# 130801_AriloRX_0_0.net
KiCad netlist of a schematic drawn in EAGLE
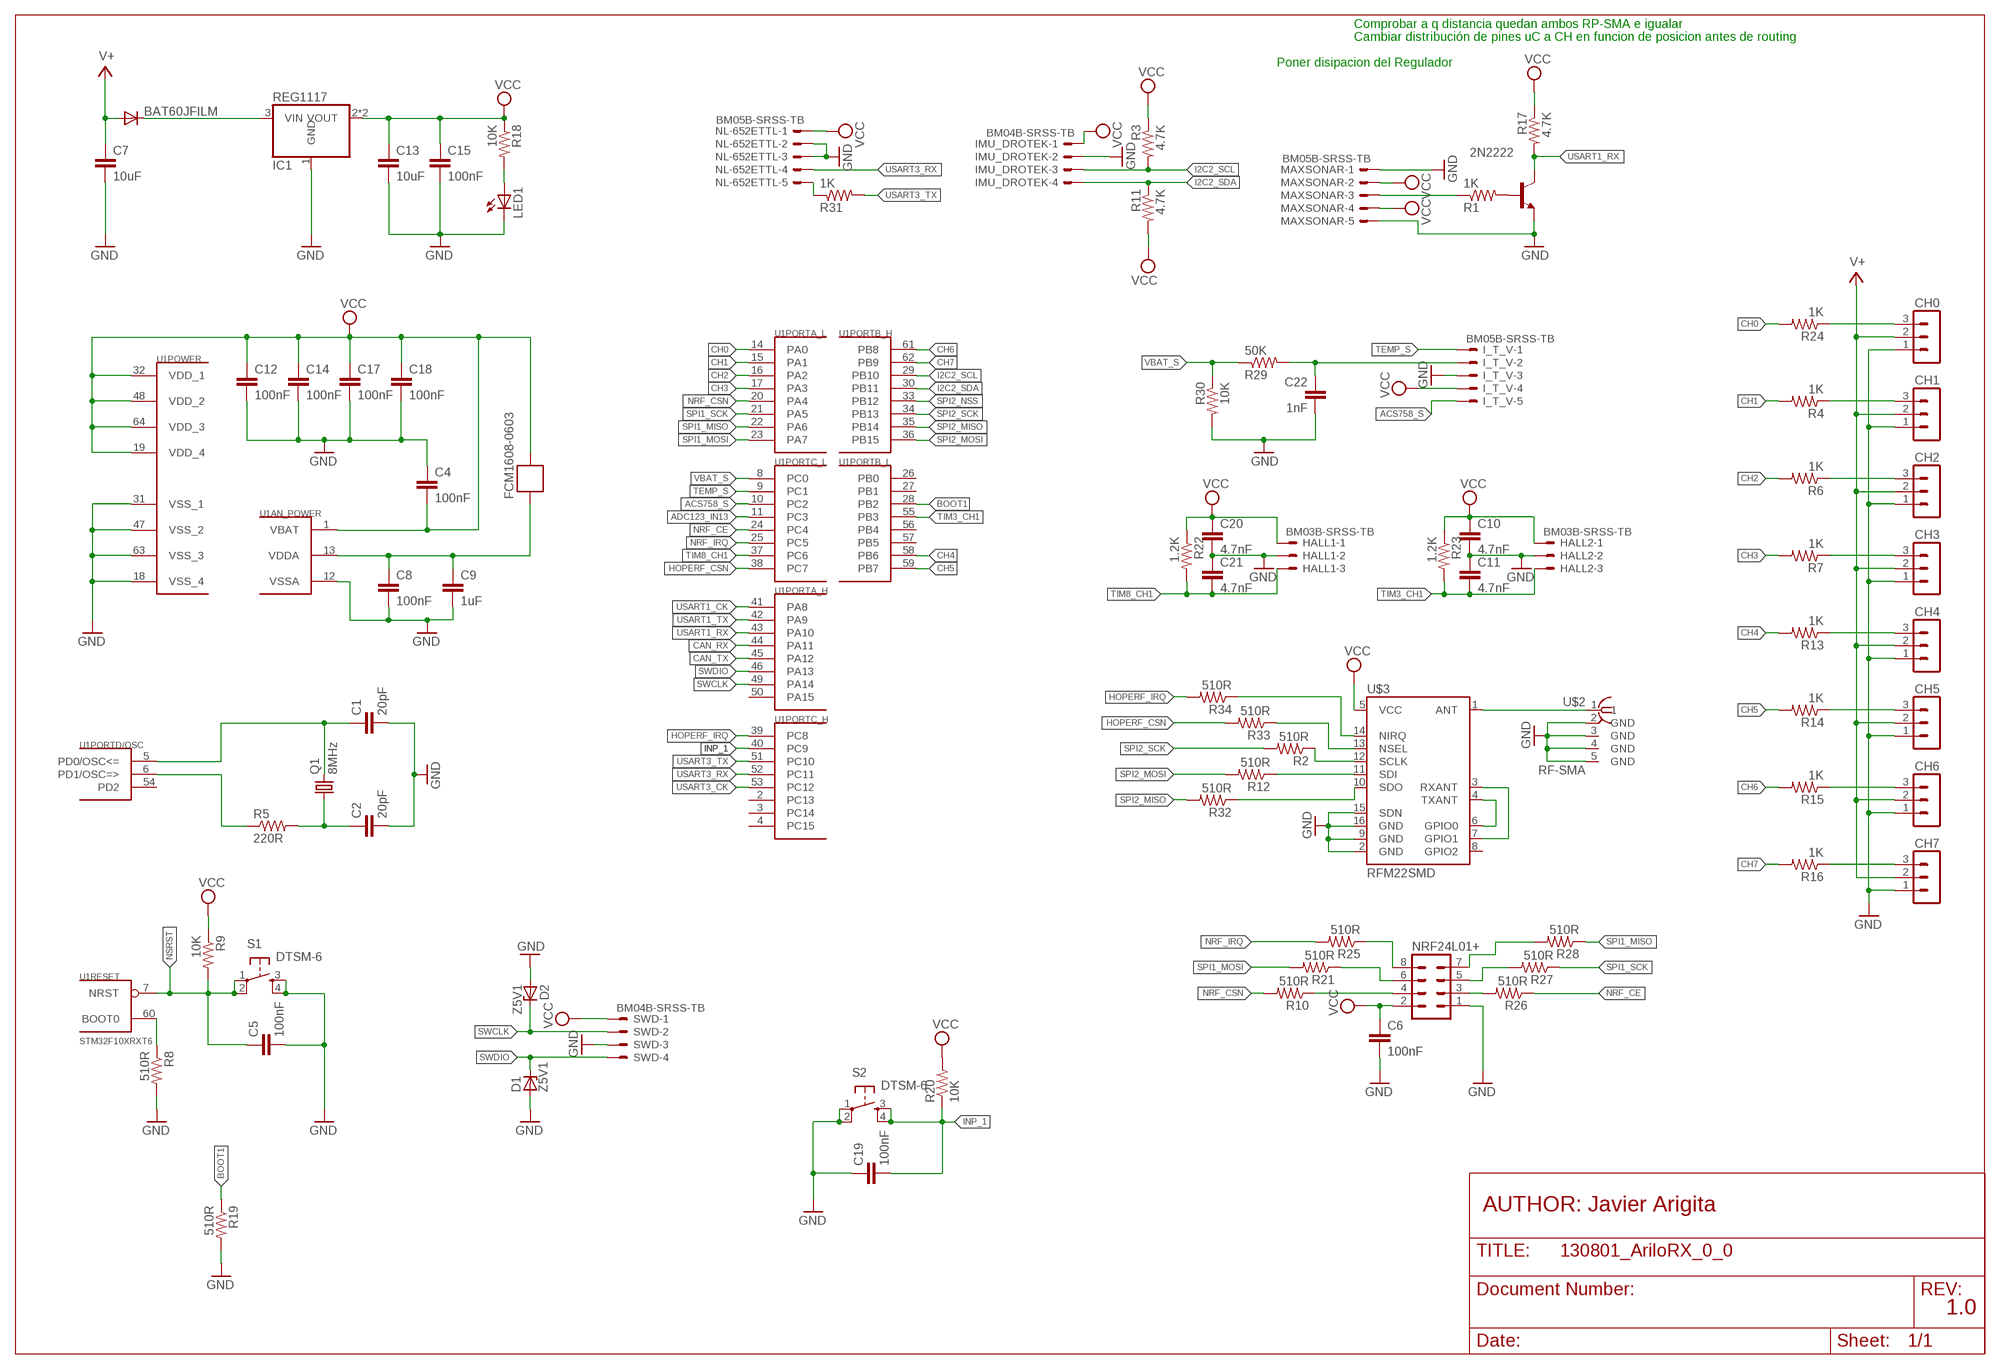
[diagram p0: schematic, sheet 1]

(export (version "E")
  (design (tool "Eeschema 10.0.6"))
  (components
    (comp (ref "2N2222")
      (value "MMBT2222ALT1-NPN-SOT23-BEC")
      (footprint "eagle-import:SOT23-BEC")
      (libsource (lib "eagle-import") (part "-NPN-SOT23-BECMMBT2222ALT1"))
    )
    (comp (ref "BAT60JFILM")
      (value "DIODE-SOD323-R")
      (footprint "eagle-import:SOD323-R")
      (libsource (lib "eagle-import") (part "DIODE-SOD323-R"))
    )
    (comp (ref "C1")
      (value "20pF")
      (footprint "eagle-import:C0805")
      (libsource (lib "eagle-import") (part "C-EUC0805"))
    )
    (comp (ref "C2")
      (value "20pF")
      (footprint "eagle-import:C0805")
      (libsource (lib "eagle-import") (part "C-EUC0805"))
    )
    (comp (ref "C4")
      (value "100nF")
      (footprint "eagle-import:C0805")
      (libsource (lib "eagle-import") (part "C-EUC0805"))
    )
    (comp (ref "C5")
      (value "100nF")
      (footprint "eagle-import:C0805")
      (libsource (lib "eagle-import") (part "C-EUC0805"))
    )
    (comp (ref "C6")
      (value "100nF")
      (footprint "eagle-import:C0805")
      (libsource (lib "eagle-import") (part "C-EUC0805"))
    )
    (comp (ref "C7")
      (value "10uF")
      (footprint "eagle-import:C3216")
      (libsource (lib "eagle-import") (part "resistor_C-EUC3216"))
    )
    (comp (ref "C8")
      (value "100nF")
      (footprint "eagle-import:C0805")
      (libsource (lib "eagle-import") (part "C-EUC0805"))
    )
    (comp (ref "C9")
      (value "1uF")
      (footprint "eagle-import:C3216")
      (libsource (lib "eagle-import") (part "resistor_C-EUC3216"))
    )
    (comp (ref "C10")
      (value "4.7nF")
      (footprint "eagle-import:C0805")
      (libsource (lib "eagle-import") (part "C-EUC0805"))
    )
    (comp (ref "C11")
      (value "4.7nF")
      (footprint "eagle-import:C0805")
      (libsource (lib "eagle-import") (part "C-EUC0805"))
    )
    (comp (ref "C12")
      (value "100nF")
      (footprint "eagle-import:C0805")
      (libsource (lib "eagle-import") (part "C-EUC0805"))
    )
    (comp (ref "C13")
      (value "10uF")
      (footprint "eagle-import:C3216")
      (libsource (lib "eagle-import") (part "resistor_C-EUC3216"))
    )
    (comp (ref "C14")
      (value "100nF")
      (footprint "eagle-import:C0805")
      (libsource (lib "eagle-import") (part "C-EUC0805"))
    )
    (comp (ref "C15")
      (value "100nF")
      (footprint "eagle-import:C0805")
      (libsource (lib "eagle-import") (part "C-EUC0805"))
    )
    (comp (ref "C17")
      (value "100nF")
      (footprint "eagle-import:C0805")
      (libsource (lib "eagle-import") (part "C-EUC0805"))
    )
    (comp (ref "C18")
      (value "100nF")
      (footprint "eagle-import:C0805")
      (libsource (lib "eagle-import") (part "C-EUC0805"))
    )
    (comp (ref "C19")
      (value "100nF")
      (footprint "eagle-import:C0805")
      (libsource (lib "eagle-import") (part "C-EUC0805"))
    )
    (comp (ref "C20")
      (value "4.7nF")
      (footprint "eagle-import:C0805")
      (libsource (lib "eagle-import") (part "C-EUC0805"))
    )
    (comp (ref "C21")
      (value "4.7nF")
      (footprint "eagle-import:C0805")
      (libsource (lib "eagle-import") (part "C-EUC0805"))
    )
    (comp (ref "C22")
      (value "1nF")
      (footprint "eagle-import:C0805")
      (libsource (lib "eagle-import") (part "C-EUC0805"))
    )
    (comp (ref "CH0")
      (value "MA03-1")
      (footprint "eagle-import:MA03-1")
      (libsource (lib "eagle-import") (part "MA03-1"))
    )
    (comp (ref "CH1")
      (value "MA03-1")
      (footprint "eagle-import:MA03-1")
      (libsource (lib "eagle-import") (part "MA03-1"))
    )
    (comp (ref "CH2")
      (value "MA03-1")
      (footprint "eagle-import:MA03-1")
      (libsource (lib "eagle-import") (part "MA03-1"))
    )
    (comp (ref "CH3")
      (value "MA03-1")
      (footprint "eagle-import:MA03-1")
      (libsource (lib "eagle-import") (part "MA03-1"))
    )
    (comp (ref "CH4")
      (value "MA03-1")
      (footprint "eagle-import:MA03-1")
      (libsource (lib "eagle-import") (part "MA03-1"))
    )
    (comp (ref "CH5")
      (value "MA03-1")
      (footprint "eagle-import:MA03-1")
      (libsource (lib "eagle-import") (part "MA03-1"))
    )
    (comp (ref "CH6")
      (value "MA03-1")
      (footprint "eagle-import:MA03-1")
      (libsource (lib "eagle-import") (part "MA03-1"))
    )
    (comp (ref "CH7")
      (value "MA03-1")
      (footprint "eagle-import:MA03-1")
      (libsource (lib "eagle-import") (part "MA03-1"))
    )
    (comp (ref "D1")
      (value "Z5V1")
      (footprint "eagle-import:SOD80C")
      (libsource (lib "eagle-import") (part "ZENER-DIODESOD80C"))
    )
    (comp (ref "D2")
      (value "Z5V1")
      (footprint "eagle-import:SOD80C")
      (libsource (lib "eagle-import") (part "ZENER-DIODESOD80C"))
    )
    (comp (ref "FCM1608-0603")
      (value "FERRITE-BEAD")
      (footprint "eagle-import:R0603")
      (libsource (lib "eagle-import") (part "FERRITE-BEAD"))
    )
    (comp (ref "HALL1")
      (value "BM03B-SRSS-TB")
      (footprint "eagle-import:BM03B-SRSS-TB")
      (libsource (lib "eagle-import") (part "?M03B-SRSS-TBB"))
    )
    (comp (ref "HALL2")
      (value "BM03B-SRSS-TB")
      (footprint "eagle-import:BM03B-SRSS-TB")
      (libsource (lib "eagle-import") (part "?M03B-SRSS-TBB"))
    )
    (comp (ref "IC1")
      (value "REG1117")
      (footprint "eagle-import:SOT223")
      (libsource (lib "eagle-import") (part "REG1117"))
    )
    (comp (ref "IMU_DROTEK")
      (value "BM04B-SRSS-TB")
      (footprint "eagle-import:BM04B-SRSS-TB")
      (libsource (lib "eagle-import") (part "?M04B-SRSS-TBB"))
    )
    (comp (ref "I_T_V")
      (value "BM05B-SRSS-TB")
      (footprint "eagle-import:BM05B-SRSS-TB")
      (libsource (lib "eagle-import") (part "?M05B-SRSS-TBB"))
    )
    (comp (ref "LED1")
      (value "LED0805")
      (footprint "eagle-import:CHIPLED_0805")
      (libsource (lib "eagle-import") (part "LED0805"))
    )
    (comp (ref "MAXSONAR")
      (value "BM05B-SRSS-TB")
      (footprint "eagle-import:BM05B-SRSS-TB")
      (libsource (lib "eagle-import") (part "?M05B-SRSS-TBB"))
    )
    (comp (ref "NL-652ETTL")
      (value "BM05B-SRSS-TB")
      (footprint "eagle-import:BM05B-SRSS-TB")
      (libsource (lib "eagle-import") (part "?M05B-SRSS-TBB"))
    )
    (comp (ref "NRF24L01+")
      (value "MA04-2")
      (footprint "eagle-import:MA04-2")
      (libsource (lib "eagle-import") (part "MA04-2"))
    )
    (comp (ref "Q1")
      (value "8MHz")
      (footprint "eagle-import:SM49")
      (libsource (lib "eagle-import") (part "CRYSTALSM49"))
    )
    (comp (ref "R1")
      (value "1K")
      (footprint "eagle-import:R0805")
      (libsource (lib "eagle-import") (part "RESISTOR0805"))
    )
    (comp (ref "R2")
      (value "510R")
      (footprint "eagle-import:R0805")
      (libsource (lib "eagle-import") (part "RESISTOR0805"))
    )
    (comp (ref "R3")
      (value "4.7K")
      (footprint "eagle-import:R0805")
      (libsource (lib "eagle-import") (part "RESISTOR0805"))
    )
    (comp (ref "R4")
      (value "1K")
      (footprint "eagle-import:R0805")
      (libsource (lib "eagle-import") (part "RESISTOR0805"))
    )
    (comp (ref "R5")
      (value "220R")
      (footprint "eagle-import:R0805")
      (libsource (lib "eagle-import") (part "RESISTOR0805"))
    )
    (comp (ref "R6")
      (value "1K")
      (footprint "eagle-import:R0805")
      (libsource (lib "eagle-import") (part "RESISTOR0805"))
    )
    (comp (ref "R7")
      (value "1K")
      (footprint "eagle-import:R0805")
      (libsource (lib "eagle-import") (part "RESISTOR0805"))
    )
    (comp (ref "R8")
      (value "510R")
      (footprint "eagle-import:R0805")
      (libsource (lib "eagle-import") (part "RESISTOR0805"))
    )
    (comp (ref "R9")
      (value "10K")
      (footprint "eagle-import:R0805")
      (libsource (lib "eagle-import") (part "RESISTOR0805"))
    )
    (comp (ref "R10")
      (value "510R")
      (footprint "eagle-import:R0805")
      (libsource (lib "eagle-import") (part "RESISTOR0805"))
    )
    (comp (ref "R11")
      (value "4.7K")
      (footprint "eagle-import:R0805")
      (libsource (lib "eagle-import") (part "RESISTOR0805"))
    )
    (comp (ref "R12")
      (value "510R")
      (footprint "eagle-import:R0805")
      (libsource (lib "eagle-import") (part "RESISTOR0805"))
    )
    (comp (ref "R13")
      (value "1K")
      (footprint "eagle-import:R0805")
      (libsource (lib "eagle-import") (part "RESISTOR0805"))
    )
    (comp (ref "R14")
      (value "1K")
      (footprint "eagle-import:R0805")
      (libsource (lib "eagle-import") (part "RESISTOR0805"))
    )
    (comp (ref "R15")
      (value "1K")
      (footprint "eagle-import:R0805")
      (libsource (lib "eagle-import") (part "RESISTOR0805"))
    )
    (comp (ref "R16")
      (value "1K")
      (footprint "eagle-import:R0805")
      (libsource (lib "eagle-import") (part "RESISTOR0805"))
    )
    (comp (ref "R17")
      (value "4.7K")
      (footprint "eagle-import:R0805")
      (libsource (lib "eagle-import") (part "RESISTOR0805"))
    )
    (comp (ref "R18")
      (value "10K")
      (footprint "eagle-import:R0805")
      (libsource (lib "eagle-import") (part "RESISTOR0805"))
    )
    (comp (ref "R19")
      (value "510R")
      (footprint "eagle-import:R0805")
      (libsource (lib "eagle-import") (part "RESISTOR0805"))
    )
    (comp (ref "R20")
      (value "10K")
      (footprint "eagle-import:R0805")
      (libsource (lib "eagle-import") (part "RESISTOR0805"))
    )
    (comp (ref "R21")
      (value "510R")
      (footprint "eagle-import:R0805")
      (libsource (lib "eagle-import") (part "RESISTOR0805"))
    )
    (comp (ref "R22")
      (value "1.2K")
      (footprint "eagle-import:R0805")
      (libsource (lib "eagle-import") (part "RESISTOR0805"))
    )
    (comp (ref "R23")
      (value "1.2K")
      (footprint "eagle-import:R0805")
      (libsource (lib "eagle-import") (part "RESISTOR0805"))
    )
    (comp (ref "R24")
      (value "1K")
      (footprint "eagle-import:R0805")
      (libsource (lib "eagle-import") (part "RESISTOR0805"))
    )
    (comp (ref "R25")
      (value "510R")
      (footprint "eagle-import:R0805")
      (libsource (lib "eagle-import") (part "RESISTOR0805"))
    )
    (comp (ref "R26")
      (value "510R")
      (footprint "eagle-import:R0805")
      (libsource (lib "eagle-import") (part "RESISTOR0805"))
    )
    (comp (ref "R27")
      (value "510R")
      (footprint "eagle-import:R0805")
      (libsource (lib "eagle-import") (part "RESISTOR0805"))
    )
    (comp (ref "R28")
      (value "510R")
      (footprint "eagle-import:R0805")
      (libsource (lib "eagle-import") (part "RESISTOR0805"))
    )
    (comp (ref "R29")
      (value "50K")
      (footprint "eagle-import:R0805")
      (libsource (lib "eagle-import") (part "RESISTOR0805"))
    )
    (comp (ref "R30")
      (value "10K")
      (footprint "eagle-import:R0805")
      (libsource (lib "eagle-import") (part "RESISTOR0805"))
    )
    (comp (ref "R31")
      (value "1K")
      (footprint "eagle-import:R0805")
      (libsource (lib "eagle-import") (part "RESISTOR0805"))
    )
    (comp (ref "R32")
      (value "510R")
      (footprint "eagle-import:R0805")
      (libsource (lib "eagle-import") (part "RESISTOR0805"))
    )
    (comp (ref "R33")
      (value "510R")
      (footprint "eagle-import:R0805")
      (libsource (lib "eagle-import") (part "RESISTOR0805"))
    )
    (comp (ref "R34")
      (value "510R")
      (footprint "eagle-import:R0805")
      (libsource (lib "eagle-import") (part "RESISTOR0805"))
    )
    (comp (ref "S1")
      (value "DTSM-6")
      (footprint "eagle-import:DTSM-6")
      (libsource (lib "eagle-import") (part "DTSM-6"))
    )
    (comp (ref "S2")
      (value "DTSM-6")
      (footprint "eagle-import:DTSM-6")
      (libsource (lib "eagle-import") (part "DTSM-6"))
    )
    (comp (ref "SWD")
      (value "BM04B-SRSS-TB")
      (footprint "eagle-import:BM04B-SRSS-TB")
      (libsource (lib "eagle-import") (part "?M04B-SRSS-TBB"))
    )
    (comp (ref "U$2")
      (value "RF-SMA")
      (footprint "eagle-import:BU-SMA-H")
      (libsource (lib "eagle-import") (part "RF-SMA"))
    )
    (comp (ref "U$3")
      (value "RFM22SMD")
      (footprint "eagle-import:RFM22-XXX-S2")
      (libsource (lib "eagle-import") (part "RFM22SMD"))
    )
    (comp (ref "U1")
      (value "STM32F10XRXT6")
      (footprint "eagle-import:TQFP64")
      (libsource (lib "eagle-import") (part "STM32F10XRXT6"))
    )
  )
  (nets
    (net (code "1") (name "ACS758_S") (class "Default")
      (node (ref "I_T_V") (pin "5") (pinfunction "S_5") (pintype "passive"))
      (node (ref "U1") (pin "10") (pinfunction "PC2_10") (pintype "bidirectional"))
    )
    (net (code "2") (name "ADC123_IN13") (class "Default")
      (node (ref "U1") (pin "11") (pinfunction "PC3_11") (pintype "bidirectional"))
    )
    (net (code "3") (name "BOOT1") (class "Default")
      (node (ref "R19") (pin "1") (pinfunction "1_1") (pintype "passive"))
      (node (ref "U1") (pin "28") (pinfunction "PB2_28") (pintype "bidirectional"))
    )
    (net (code "4") (name "CAN_RX") (class "Default")
      (node (ref "U1") (pin "44") (pinfunction "PA11_44") (pintype "bidirectional"))
    )
    (net (code "5") (name "CAN_TX") (class "Default")
      (node (ref "U1") (pin "45") (pinfunction "PA12_45") (pintype "bidirectional"))
    )
    (net (code "6") (name "CH0") (class "Default")
      (node (ref "R24") (pin "2") (pinfunction "2_2") (pintype "passive"))
      (node (ref "U1") (pin "14") (pinfunction "PA0_14") (pintype "bidirectional"))
    )
    (net (code "7") (name "CH1") (class "Default")
      (node (ref "R4") (pin "2") (pinfunction "2_2") (pintype "passive"))
      (node (ref "U1") (pin "15") (pinfunction "PA1_15") (pintype "bidirectional"))
    )
    (net (code "8") (name "CH2") (class "Default")
      (node (ref "R6") (pin "2") (pinfunction "2_2") (pintype "passive"))
      (node (ref "U1") (pin "16") (pinfunction "PA2_16") (pintype "bidirectional"))
    )
    (net (code "9") (name "CH3") (class "Default")
      (node (ref "R7") (pin "2") (pinfunction "2_2") (pintype "passive"))
      (node (ref "U1") (pin "17") (pinfunction "PA3_17") (pintype "bidirectional"))
    )
    (net (code "10") (name "CH4") (class "Default")
      (node (ref "R13") (pin "2") (pinfunction "2_2") (pintype "passive"))
      (node (ref "U1") (pin "58") (pinfunction "PB6_58") (pintype "bidirectional"))
    )
    (net (code "11") (name "CH5") (class "Default")
      (node (ref "R14") (pin "2") (pinfunction "2_2") (pintype "passive"))
      (node (ref "U1") (pin "59") (pinfunction "PB7_59") (pintype "bidirectional"))
    )
    (net (code "12") (name "CH6") (class "Default")
      (node (ref "R15") (pin "2") (pinfunction "2_2") (pintype "passive"))
      (node (ref "U1") (pin "61") (pinfunction "PB8_61") (pintype "bidirectional"))
    )
    (net (code "13") (name "CH7") (class "Default")
      (node (ref "R16") (pin "2") (pinfunction "2_2") (pintype "passive"))
      (node (ref "U1") (pin "62") (pinfunction "PB9_62") (pintype "bidirectional"))
    )
    (net (code "14") (name "GND") (class "Default")
      (node (ref "2N2222") (pin "E") (pinfunction "E_E") (pintype "passive"))
      (node (ref "C1") (pin "2") (pinfunction "2_2") (pintype "passive"))
      (node (ref "C10") (pin "2") (pinfunction "2_2") (pintype "passive"))
      (node (ref "C11") (pin "1") (pinfunction "1_1") (pintype "passive"))
      (node (ref "C12") (pin "2") (pinfunction "2_2") (pintype "passive"))
      (node (ref "C13") (pin "2") (pinfunction "2_2") (pintype "passive"))
      (node (ref "C14") (pin "2") (pinfunction "2_2") (pintype "passive"))
      (node (ref "C15") (pin "2") (pinfunction "2_2") (pintype "passive"))
      (node (ref "C17") (pin "2") (pinfunction "2_2") (pintype "passive"))
      (node (ref "C18") (pin "2") (pinfunction "2_2") (pintype "passive"))
      (node (ref "C19") (pin "1") (pinfunction "1_1") (pintype "passive"))
      (node (ref "C2") (pin "2") (pinfunction "2_2") (pintype "passive"))
      (node (ref "C20") (pin "2") (pinfunction "2_2") (pintype "passive"))
      (node (ref "C21") (pin "1") (pinfunction "1_1") (pintype "passive"))
      (node (ref "C22") (pin "2") (pinfunction "2_2") (pintype "passive"))
      (node (ref "C4") (pin "1") (pinfunction "1_1") (pintype "passive"))
      (node (ref "C5") (pin "2") (pinfunction "2_2") (pintype "passive"))
      (node (ref "C6") (pin "2") (pinfunction "2_2") (pintype "passive"))
      (node (ref "C7") (pin "2") (pinfunction "2_2") (pintype "passive"))
      (node (ref "C8") (pin "2") (pinfunction "2_2") (pintype "passive"))
      (node (ref "C9") (pin "2") (pinfunction "2_2") (pintype "passive"))
      (node (ref "CH0") (pin "1") (pinfunction "1_1") (pintype "passive"))
      (node (ref "CH1") (pin "1") (pinfunction "1_1") (pintype "passive"))
      (node (ref "CH2") (pin "1") (pinfunction "1_1") (pintype "passive"))
      (node (ref "CH3") (pin "1") (pinfunction "1_1") (pintype "passive"))
      (node (ref "CH4") (pin "1") (pinfunction "1_1") (pintype "passive"))
      (node (ref "CH5") (pin "1") (pinfunction "1_1") (pintype "passive"))
      (node (ref "CH6") (pin "1") (pinfunction "1_1") (pintype "passive"))
      (node (ref "CH7") (pin "1") (pinfunction "1_1") (pintype "passive"))
      (node (ref "D1") (pin "A") (pinfunction "A_A") (pintype "passive"))
      (node (ref "D2") (pin "A") (pinfunction "A_A") (pintype "passive"))
      (node (ref "HALL1") (pin "2") (pinfunction "S_2") (pintype "passive"))
      (node (ref "HALL2") (pin "2") (pinfunction "S_2") (pintype "passive"))
      (node (ref "IC1") (pin "1") (pinfunction "GND_1") (pintype "power_in"))
      (node (ref "IMU_DROTEK") (pin "2") (pinfunction "S_2") (pintype "passive"))
      (node (ref "I_T_V") (pin "3") (pinfunction "S_3") (pintype "passive"))
      (node (ref "LED1") (pin "C") (pinfunction "C_C") (pintype "passive"))
      (node (ref "MAXSONAR") (pin "1") (pinfunction "S_1") (pintype "passive"))
      (node (ref "MAXSONAR") (pin "5") (pinfunction "S_5") (pintype "passive"))
      (node (ref "NL-652ETTL") (pin "2") (pinfunction "S_2") (pintype "passive"))
      (node (ref "NL-652ETTL") (pin "3") (pinfunction "S_3") (pintype "passive"))
      (node (ref "NRF24L01+") (pin "1") (pinfunction "1_1") (pintype "passive"))
      (node (ref "R19") (pin "2") (pinfunction "2_2") (pintype "passive"))
      (node (ref "R30") (pin "2") (pinfunction "2_2") (pintype "passive"))
      (node (ref "R8") (pin "2") (pinfunction "2_2") (pintype "passive"))
      (node (ref "S1") (pin "3") (pinfunction "3_3") (pintype "passive"))
      (node (ref "S1") (pin "4") (pinfunction "4_4") (pintype "passive"))
      (node (ref "S2") (pin "1") (pinfunction "1_1") (pintype "passive"))
      (node (ref "S2") (pin "2") (pinfunction "2_2") (pintype "passive"))
      (node (ref "SWD") (pin "3") (pinfunction "S_3") (pintype "passive"))
      (node (ref "U$2") (pin "2") (pinfunction "GND_2") (pintype "power_in"))
      (node (ref "U$2") (pin "3") (pinfunction "GND_3") (pintype "bidirectional"))
      (node (ref "U$2") (pin "4") (pinfunction "GND_4") (pintype "bidirectional"))
      (node (ref "U$2") (pin "5") (pinfunction "GND_5") (pintype "bidirectional"))
      (node (ref "U$3") (pin "15") (pinfunction "SDN_15") (pintype "input"))
      (node (ref "U$3") (pin "16") (pinfunction "GND_16") (pintype "power_in"))
      (node (ref "U$3") (pin "2") (pinfunction "GND_2") (pintype "power_in"))
      (node (ref "U$3") (pin "9") (pinfunction "GND_9") (pintype "power_in"))
      (node (ref "U1") (pin "12") (pinfunction "VSSA_12") (pintype "power_in"))
      (node (ref "U1") (pin "18") (pinfunction "VSS_4_18") (pintype "power_in"))
      (node (ref "U1") (pin "31") (pinfunction "VSS_1_31") (pintype "power_in"))
      (node (ref "U1") (pin "47") (pinfunction "VSS_2_47") (pintype "power_in"))
      (node (ref "U1") (pin "63") (pinfunction "VSS_3_63") (pintype "power_in"))
    )
    (net (code "15") (name "HOPERF_CSN") (class "Default")
      (node (ref "R33") (pin "2") (pinfunction "2_2") (pintype "passive"))
      (node (ref "U1") (pin "38") (pinfunction "PC7_38") (pintype "bidirectional"))
    )
    (net (code "16") (name "HOPERF_IRQ") (class "Default")
      (node (ref "R34") (pin "2") (pinfunction "2_2") (pintype "passive"))
      (node (ref "U1") (pin "39") (pinfunction "PC8_39") (pintype "bidirectional"))
    )
    (net (code "17") (name "I2C2_SCL") (class "Default")
      (node (ref "IMU_DROTEK") (pin "3") (pinfunction "S_3") (pintype "passive"))
      (node (ref "R3") (pin "2") (pinfunction "2_2") (pintype "passive"))
      (node (ref "U1") (pin "29") (pinfunction "PB10_29") (pintype "bidirectional"))
    )
    (net (code "18") (name "I2C2_SDA") (class "Default")
      (node (ref "IMU_DROTEK") (pin "4") (pinfunction "S_4") (pintype "passive"))
      (node (ref "R11") (pin "1") (pinfunction "1_1") (pintype "passive"))
      (node (ref "U1") (pin "30") (pinfunction "PB11_30") (pintype "bidirectional"))
    )
    (net (code "19") (name "INP_1") (class "Default")
      (node (ref "C19") (pin "2") (pinfunction "2_2") (pintype "passive"))
      (node (ref "R20") (pin "1") (pinfunction "1_1") (pintype "passive"))
      (node (ref "S2") (pin "3") (pinfunction "3_3") (pintype "passive"))
      (node (ref "S2") (pin "4") (pinfunction "4_4") (pintype "passive"))
      (node (ref "U1") (pin "40") (pinfunction "PC9_40") (pintype "bidirectional"))
    )
    (net (code "20") (name "NRF_CE") (class "Default")
      (node (ref "R26") (pin "1") (pinfunction "1_1") (pintype "passive"))
      (node (ref "U1") (pin "24") (pinfunction "PC4_24") (pintype "bidirectional"))
    )
    (net (code "21") (name "NRF_CSN") (class "Default")
      (node (ref "R10") (pin "2") (pinfunction "2_2") (pintype "passive"))
      (node (ref "U1") (pin "20") (pinfunction "PA4_20") (pintype "bidirectional"))
    )
    (net (code "22") (name "NRF_IRQ") (class "Default")
      (node (ref "R25") (pin "2") (pinfunction "2_2") (pintype "passive"))
      (node (ref "U1") (pin "25") (pinfunction "PC5_25") (pintype "bidirectional"))
    )
    (net (code "23") (name "NSRST") (class "Default")
      (node (ref "C5") (pin "1") (pinfunction "1_1") (pintype "passive"))
      (node (ref "R9") (pin "2") (pinfunction "2_2") (pintype "passive"))
      (node (ref "S1") (pin "1") (pinfunction "1_1") (pintype "passive"))
      (node (ref "S1") (pin "2") (pinfunction "2_2") (pintype "passive"))
      (node (ref "U1") (pin "7") (pinfunction "NRST_7") (pintype "input"))
    )
    (net (code "24") (name "Net-(2N2222-PadB)") (class "Default")
      (node (ref "2N2222") (pin "B") (pinfunction "B_B") (pintype "passive"))
      (node (ref "R1") (pin "2") (pinfunction "2_2") (pintype "passive"))
    )
    (net (code "25") (name "Net-(C2-Pad1)") (class "Default")
      (node (ref "C2") (pin "1") (pinfunction "1_1") (pintype "passive"))
      (node (ref "Q1") (pin "1") (pinfunction "1_1") (pintype "passive"))
      (node (ref "R5") (pin "2") (pinfunction "2_2") (pintype "passive"))
    )
    (net (code "26") (name "Net-(CH0-Pad3)") (class "Default")
      (node (ref "CH0") (pin "3") (pinfunction "3_3") (pintype "passive"))
      (node (ref "R24") (pin "1") (pinfunction "1_1") (pintype "passive"))
    )
    (net (code "27") (name "Net-(CH1-Pad3)") (class "Default")
      (node (ref "CH1") (pin "3") (pinfunction "3_3") (pintype "passive"))
      (node (ref "R4") (pin "1") (pinfunction "1_1") (pintype "passive"))
    )
    (net (code "28") (name "Net-(CH2-Pad3)") (class "Default")
      (node (ref "CH2") (pin "3") (pinfunction "3_3") (pintype "passive"))
      (node (ref "R6") (pin "1") (pinfunction "1_1") (pintype "passive"))
    )
    (net (code "29") (name "Net-(CH3-Pad3)") (class "Default")
      (node (ref "CH3") (pin "3") (pinfunction "3_3") (pintype "passive"))
      (node (ref "R7") (pin "1") (pinfunction "1_1") (pintype "passive"))
    )
    (net (code "30") (name "Net-(CH4-Pad3)") (class "Default")
      (node (ref "CH4") (pin "3") (pinfunction "3_3") (pintype "passive"))
      (node (ref "R13") (pin "1") (pinfunction "1_1") (pintype "passive"))
    )
    (net (code "31") (name "Net-(CH5-Pad3)") (class "Default")
      (node (ref "CH5") (pin "3") (pinfunction "3_3") (pintype "passive"))
      (node (ref "R14") (pin "1") (pinfunction "1_1") (pintype "passive"))
    )
    (net (code "32") (name "Net-(CH6-Pad3)") (class "Default")
      (node (ref "CH6") (pin "3") (pinfunction "3_3") (pintype "passive"))
      (node (ref "R15") (pin "1") (pinfunction "1_1") (pintype "passive"))
    )
    (net (code "33") (name "Net-(CH7-Pad3)") (class "Default")
      (node (ref "CH7") (pin "3") (pinfunction "3_3") (pintype "passive"))
      (node (ref "R16") (pin "1") (pinfunction "1_1") (pintype "passive"))
    )
    (net (code "34") (name "Net-(FCM1608-0603-P$2)") (class "Default")
      (node (ref "C8") (pin "1") (pinfunction "1_1") (pintype "passive"))
      (node (ref "C9") (pin "1") (pinfunction "1_1") (pintype "passive"))
      (node (ref "FCM1608-0603") (pin "2") (pinfunction "P$2_2") (pintype "bidirectional"))
      (node (ref "U1") (pin "13") (pinfunction "VDDA_13") (pintype "power_in"))
    )
    (net (code "35") (name "Net-(IC1-VIN)") (class "Default")
      (node (ref "BAT60JFILM") (pin "C") (pinfunction "C_C") (pintype "passive"))
      (node (ref "IC1") (pin "3") (pinfunction "VIN_3") (pintype "input"))
    )
    (net (code "36") (name "Net-(I_T_VB-S)") (class "Default")
      (node (ref "C22") (pin "1") (pinfunction "1_1") (pintype "passive"))
      (node (ref "I_T_V") (pin "2") (pinfunction "S_2") (pintype "passive"))
      (node (ref "R29") (pin "2") (pinfunction "2_2") (pintype "passive"))
    )
    (net (code "37") (name "Net-(LED1-PadA)") (class "Default")
      (node (ref "LED1") (pin "A") (pinfunction "A_A") (pintype "passive"))
      (node (ref "R18") (pin "2") (pinfunction "2_2") (pintype "passive"))
    )
    (net (code "38") (name "Net-(MAXSONARC-S)") (class "Default")
      (node (ref "MAXSONAR") (pin "3") (pinfunction "S_3") (pintype "passive"))
      (node (ref "R1") (pin "1") (pinfunction "1_1") (pintype "passive"))
    )
    (net (code "39") (name "Net-(NL-652ETTLE-S)") (class "Default")
      (node (ref "NL-652ETTL") (pin "5") (pinfunction "S_5") (pintype "passive"))
      (node (ref "R31") (pin "1") (pinfunction "1_1") (pintype "passive"))
    )
    (net (code "40") (name "Net-(NRF24L01+-Pad3)") (class "Default")
      (node (ref "NRF24L01+") (pin "3") (pinfunction "3_3") (pintype "passive"))
      (node (ref "R26") (pin "2") (pinfunction "2_2") (pintype "passive"))
    )
    (net (code "41") (name "Net-(NRF24L01+-Pad4)") (class "Default")
      (node (ref "NRF24L01+") (pin "4") (pinfunction "4_4") (pintype "passive"))
      (node (ref "R10") (pin "1") (pinfunction "1_1") (pintype "passive"))
    )
    (net (code "42") (name "Net-(NRF24L01+-Pad5)") (class "Default")
      (node (ref "NRF24L01+") (pin "5") (pinfunction "5_5") (pintype "passive"))
      (node (ref "R27") (pin "2") (pinfunction "2_2") (pintype "passive"))
    )
    (net (code "43") (name "Net-(NRF24L01+-Pad6)") (class "Default")
      (node (ref "NRF24L01+") (pin "6") (pinfunction "6_6") (pintype "passive"))
      (node (ref "R21") (pin "1") (pinfunction "1_1") (pintype "passive"))
    )
    (net (code "44") (name "Net-(NRF24L01+-Pad7)") (class "Default")
      (node (ref "NRF24L01+") (pin "7") (pinfunction "7_7") (pintype "passive"))
      (node (ref "R28") (pin "2") (pinfunction "2_2") (pintype "passive"))
    )
    (net (code "45") (name "Net-(NRF24L01+-Pad8)") (class "Default")
      (node (ref "NRF24L01+") (pin "8") (pinfunction "8_8") (pintype "passive"))
      (node (ref "R25") (pin "1") (pinfunction "1_1") (pintype "passive"))
    )
    (net (code "46") (name "Net-(U$3-ANT)") (class "Default")
      (node (ref "U$2") (pin "1") (pinfunction "1_1") (pintype "passive"))
      (node (ref "U$3") (pin "1") (pinfunction "ANT_1") (pintype "bidirectional"))
    )
    (net (code "47") (name "Net-(U$3-GPIO0)") (class "Default")
      (node (ref "U$3") (pin "4") (pinfunction "TXANT_4") (pintype "input"))
      (node (ref "U$3") (pin "6") (pinfunction "GPIO0_6") (pintype "bidirectional"))
    )
    (net (code "48") (name "Net-(U$3-GPIO1)") (class "Default")
      (node (ref "U$3") (pin "3") (pinfunction "RXANT_3") (pintype "input"))
      (node (ref "U$3") (pin "7") (pinfunction "GPIO1_7") (pintype "bidirectional"))
    )
    (net (code "49") (name "Net-(U$3-NIRQ)") (class "Default")
      (node (ref "R34") (pin "1") (pinfunction "1_1") (pintype "passive"))
      (node (ref "U$3") (pin "14") (pinfunction "NIRQ_14") (pintype "output"))
    )
    (net (code "50") (name "Net-(U$3-NSEL)") (class "Default")
      (node (ref "R33") (pin "1") (pinfunction "1_1") (pintype "passive"))
      (node (ref "U$3") (pin "13") (pinfunction "NSEL_13") (pintype "input"))
    )
    (net (code "51") (name "Net-(U$3-SCLK)") (class "Default")
      (node (ref "R2") (pin "1") (pinfunction "1_1") (pintype "passive"))
      (node (ref "U$3") (pin "12") (pinfunction "SCLK_12") (pintype "input"))
    )
    (net (code "52") (name "Net-(U$3-SDI)") (class "Default")
      (node (ref "R12") (pin "1") (pinfunction "1_1") (pintype "passive"))
      (node (ref "U$3") (pin "11") (pinfunction "SDI_11") (pintype "input"))
    )
    (net (code "53") (name "Net-(U$3-SDO)") (class "Default")
      (node (ref "R32") (pin "1") (pinfunction "1_1") (pintype "passive"))
      (node (ref "U$3") (pin "10") (pinfunction "SDO_10") (pintype "output"))
    )
    (net (code "54") (name "Net-(U1H-PD0{slash}OSC<=)") (class "Default")
      (node (ref "C1") (pin "1") (pinfunction "1_1") (pintype "passive"))
      (node (ref "Q1") (pin "2") (pinfunction "2_2") (pintype "passive"))
      (node (ref "U1") (pin "5") (pinfunction "PD0/OSC<=_5") (pintype "bidirectional"))
    )
    (net (code "55") (name "Net-(U1H-PD1{slash}OSC=>)") (class "Default")
      (node (ref "R5") (pin "1") (pinfunction "1_1") (pintype "passive"))
      (node (ref "U1") (pin "6") (pinfunction "PD1/OSC=>_6") (pintype "bidirectional"))
    )
    (net (code "56") (name "Net-(U1J-BOOT0)") (class "Default")
      (node (ref "R8") (pin "1") (pinfunction "1_1") (pintype "passive"))
      (node (ref "U1") (pin "60") (pinfunction "BOOT0_60") (pintype "input"))
    )
    (net (code "57") (name "SPI1_MISO") (class "Default")
      (node (ref "R28") (pin "1") (pinfunction "1_1") (pintype "passive"))
      (node (ref "U1") (pin "22") (pinfunction "PA6_22") (pintype "bidirectional"))
    )
    (net (code "58") (name "SPI1_MOSI") (class "Default")
      (node (ref "R21") (pin "2") (pinfunction "2_2") (pintype "passive"))
      (node (ref "U1") (pin "23") (pinfunction "PA7_23") (pintype "bidirectional"))
    )
    (net (code "59") (name "SPI1_SCK") (class "Default")
      (node (ref "R27") (pin "1") (pinfunction "1_1") (pintype "passive"))
      (node (ref "U1") (pin "21") (pinfunction "PA5_21") (pintype "bidirectional"))
    )
    (net (code "60") (name "SPI2_MISO") (class "Default")
      (node (ref "R32") (pin "2") (pinfunction "2_2") (pintype "passive"))
      (node (ref "U1") (pin "35") (pinfunction "PB14_35") (pintype "bidirectional"))
    )
    (net (code "61") (name "SPI2_MOSI") (class "Default")
      (node (ref "R12") (pin "2") (pinfunction "2_2") (pintype "passive"))
      (node (ref "U1") (pin "36") (pinfunction "PB15_36") (pintype "bidirectional"))
    )
    (net (code "62") (name "SPI2_NSS") (class "Default")
      (node (ref "U1") (pin "33") (pinfunction "PB12_33") (pintype "bidirectional"))
    )
    (net (code "63") (name "SPI2_SCK") (class "Default")
      (node (ref "R2") (pin "2") (pinfunction "2_2") (pintype "passive"))
      (node (ref "U1") (pin "34") (pinfunction "PB13_34") (pintype "bidirectional"))
    )
    (net (code "64") (name "SWCLK") (class "Default")
      (node (ref "D2") (pin "C") (pinfunction "C_C") (pintype "passive"))
      (node (ref "SWD") (pin "2") (pinfunction "S_2") (pintype "passive"))
      (node (ref "U1") (pin "49") (pinfunction "PA14_49") (pintype "bidirectional"))
    )
    (net (code "65") (name "SWDIO") (class "Default")
      (node (ref "D1") (pin "C") (pinfunction "C_C") (pintype "passive"))
      (node (ref "SWD") (pin "4") (pinfunction "S_4") (pintype "passive"))
      (node (ref "U1") (pin "46") (pinfunction "PA13_46") (pintype "bidirectional"))
    )
    (net (code "66") (name "TEMP_S") (class "Default")
      (node (ref "I_T_V") (pin "1") (pinfunction "S_1") (pintype "passive"))
      (node (ref "U1") (pin "9") (pinfunction "PC1_9") (pintype "bidirectional"))
    )
    (net (code "67") (name "TIM3_CH1") (class "Default")
      (node (ref "C11") (pin "2") (pinfunction "2_2") (pintype "passive"))
      (node (ref "HALL2") (pin "3") (pinfunction "S_3") (pintype "passive"))
      (node (ref "R23") (pin "2") (pinfunction "2_2") (pintype "passive"))
      (node (ref "U1") (pin "55") (pinfunction "PB3_55") (pintype "bidirectional"))
    )
    (net (code "68") (name "TIM8_CH1") (class "Default")
      (node (ref "C21") (pin "2") (pinfunction "2_2") (pintype "passive"))
      (node (ref "HALL1") (pin "3") (pinfunction "S_3") (pintype "passive"))
      (node (ref "R22") (pin "2") (pinfunction "2_2") (pintype "passive"))
      (node (ref "U1") (pin "37") (pinfunction "PC6_37") (pintype "bidirectional"))
    )
    (net (code "69") (name "USART1_CK") (class "Default")
      (node (ref "U1") (pin "41") (pinfunction "PA8_41") (pintype "bidirectional"))
    )
    (net (code "70") (name "USART1_RX") (class "Default")
      (node (ref "2N2222") (pin "C") (pinfunction "C_C") (pintype "passive"))
      (node (ref "R17") (pin "2") (pinfunction "2_2") (pintype "passive"))
      (node (ref "U1") (pin "43") (pinfunction "PA10_43") (pintype "bidirectional"))
    )
    (net (code "71") (name "USART1_TX") (class "Default")
      (node (ref "U1") (pin "42") (pinfunction "PA9_42") (pintype "bidirectional"))
    )
    (net (code "72") (name "USART3_CK") (class "Default")
      (node (ref "U1") (pin "53") (pinfunction "PC12_53") (pintype "bidirectional"))
    )
    (net (code "73") (name "USART3_RX") (class "Default")
      (node (ref "NL-652ETTL") (pin "4") (pinfunction "S_4") (pintype "passive"))
      (node (ref "U1") (pin "52") (pinfunction "PC11_52") (pintype "bidirectional"))
    )
    (net (code "74") (name "USART3_TX") (class "Default")
      (node (ref "R31") (pin "2") (pinfunction "2_2") (pintype "passive"))
      (node (ref "U1") (pin "51") (pinfunction "PC10_51") (pintype "bidirectional"))
    )
    (net (code "75") (name "V+") (class "Default")
      (node (ref "BAT60JFILM") (pin "A") (pinfunction "A_A") (pintype "passive"))
      (node (ref "C7") (pin "1") (pinfunction "1_1") (pintype "passive"))
      (node (ref "CH0") (pin "2") (pinfunction "2_2") (pintype "passive"))
      (node (ref "CH1") (pin "2") (pinfunction "2_2") (pintype "passive"))
      (node (ref "CH2") (pin "2") (pinfunction "2_2") (pintype "passive"))
      (node (ref "CH3") (pin "2") (pinfunction "2_2") (pintype "passive"))
      (node (ref "CH4") (pin "2") (pinfunction "2_2") (pintype "passive"))
      (node (ref "CH5") (pin "2") (pinfunction "2_2") (pintype "passive"))
      (node (ref "CH6") (pin "2") (pinfunction "2_2") (pintype "passive"))
      (node (ref "CH7") (pin "2") (pinfunction "2_2") (pintype "passive"))
    )
    (net (code "76") (name "VBAT_S") (class "Default")
      (node (ref "R29") (pin "1") (pinfunction "1_1") (pintype "passive"))
      (node (ref "R30") (pin "1") (pinfunction "1_1") (pintype "passive"))
      (node (ref "U1") (pin "8") (pinfunction "PC0_8") (pintype "bidirectional"))
    )
    (net (code "77") (name "VCC") (class "Default")
      (node (ref "C10") (pin "1") (pinfunction "1_1") (pintype "passive"))
      (node (ref "C12") (pin "1") (pinfunction "1_1") (pintype "passive"))
      (node (ref "C13") (pin "1") (pinfunction "1_1") (pintype "passive"))
      (node (ref "C14") (pin "1") (pinfunction "1_1") (pintype "passive"))
      (node (ref "C15") (pin "1") (pinfunction "1_1") (pintype "passive"))
      (node (ref "C17") (pin "1") (pinfunction "1_1") (pintype "passive"))
      (node (ref "C18") (pin "1") (pinfunction "1_1") (pintype "passive"))
      (node (ref "C20") (pin "1") (pinfunction "1_1") (pintype "passive"))
      (node (ref "C4") (pin "2") (pinfunction "2_2") (pintype "passive"))
      (node (ref "C6") (pin "1") (pinfunction "1_1") (pintype "passive"))
      (node (ref "FCM1608-0603") (pin "1") (pinfunction "P$1_1") (pintype "bidirectional"))
      (node (ref "HALL1") (pin "1") (pinfunction "S_1") (pintype "passive"))
      (node (ref "HALL2") (pin "1") (pinfunction "S_1") (pintype "passive"))
      (node (ref "IC1") (pin "2") (pinfunction "VOUT_2") (pintype "power_in"))
      (node (ref "IC1") (pin "4") (pinfunction "VOUT_4") (pintype "power_in"))
      (node (ref "IMU_DROTEK") (pin "1") (pinfunction "S_1") (pintype "passive"))
      (node (ref "I_T_V") (pin "4") (pinfunction "S_4") (pintype "passive"))
      (node (ref "MAXSONAR") (pin "2") (pinfunction "S_2") (pintype "passive"))
      (node (ref "MAXSONAR") (pin "4") (pinfunction "S_4") (pintype "passive"))
      (node (ref "NL-652ETTL") (pin "1") (pinfunction "S_1") (pintype "passive"))
      (node (ref "NRF24L01+") (pin "2") (pinfunction "2_2") (pintype "passive"))
      (node (ref "R11") (pin "2") (pinfunction "2_2") (pintype "passive"))
      (node (ref "R17") (pin "1") (pinfunction "1_1") (pintype "passive"))
      (node (ref "R18") (pin "1") (pinfunction "1_1") (pintype "passive"))
      (node (ref "R20") (pin "2") (pinfunction "2_2") (pintype "passive"))
      (node (ref "R22") (pin "1") (pinfunction "1_1") (pintype "passive"))
      (node (ref "R23") (pin "1") (pinfunction "1_1") (pintype "passive"))
      (node (ref "R3") (pin "1") (pinfunction "1_1") (pintype "passive"))
      (node (ref "R9") (pin "1") (pinfunction "1_1") (pintype "passive"))
      (node (ref "SWD") (pin "1") (pinfunction "S_1") (pintype "passive"))
      (node (ref "U$3") (pin "5") (pinfunction "VCC_5") (pintype "bidirectional"))
      (node (ref "U1") (pin "1") (pinfunction "VBAT_1") (pintype "power_in"))
      (node (ref "U1") (pin "19") (pinfunction "VDD_4_19") (pintype "power_in"))
      (node (ref "U1") (pin "32") (pinfunction "VDD_1_32") (pintype "power_in"))
      (node (ref "U1") (pin "48") (pinfunction "VDD_2_48") (pintype "power_in"))
      (node (ref "U1") (pin "64") (pinfunction "VDD_3_64") (pintype "power_in"))
    )
    (net (code "78") (name "unconnected-(U$3-GPIO2-Pad8)") (class "Default")
      (node (ref "U$3") (pin "8") (pinfunction "GPIO2_8") (pintype "bidirectional"))
    )
    (net (code "79") (name "unconnected-(U1B-PA15-Pad50)") (class "Default")
      (node (ref "U1") (pin "50") (pinfunction "PA15_50") (pintype "bidirectional"))
    )
    (net (code "80") (name "unconnected-(U1E-PB0-Pad26)") (class "Default")
      (node (ref "U1") (pin "26") (pinfunction "PB0_26") (pintype "bidirectional"))
    )
    (net (code "81") (name "unconnected-(U1E-PB1-Pad27)") (class "Default")
      (node (ref "U1") (pin "27") (pinfunction "PB1_27") (pintype "bidirectional"))
    )
    (net (code "82") (name "unconnected-(U1E-PB4-Pad56)") (class "Default")
      (node (ref "U1") (pin "56") (pinfunction "PB4_56") (pintype "bidirectional"))
    )
    (net (code "83") (name "unconnected-(U1E-PB5-Pad57)") (class "Default")
      (node (ref "U1") (pin "57") (pinfunction "PB5_57") (pintype "bidirectional"))
    )
    (net (code "84") (name "unconnected-(U1F-PC13-Pad2)") (class "Default")
      (node (ref "U1") (pin "2") (pinfunction "PC13_2") (pintype "bidirectional"))
    )
    (net (code "85") (name "unconnected-(U1F-PC14-Pad3)") (class "Default")
      (node (ref "U1") (pin "3") (pinfunction "PC14_3") (pintype "bidirectional"))
    )
    (net (code "86") (name "unconnected-(U1F-PC15-Pad4)") (class "Default")
      (node (ref "U1") (pin "4") (pinfunction "PC15_4") (pintype "bidirectional"))
    )
    (net (code "87") (name "unconnected-(U1H-PD2-Pad54)") (class "Default")
      (node (ref "U1") (pin "54") (pinfunction "PD2_54") (pintype "bidirectional"))
    )
  )
)
